# P06_PHY_1.net
KiCad netlist of a schematic drawn in Altium Designer
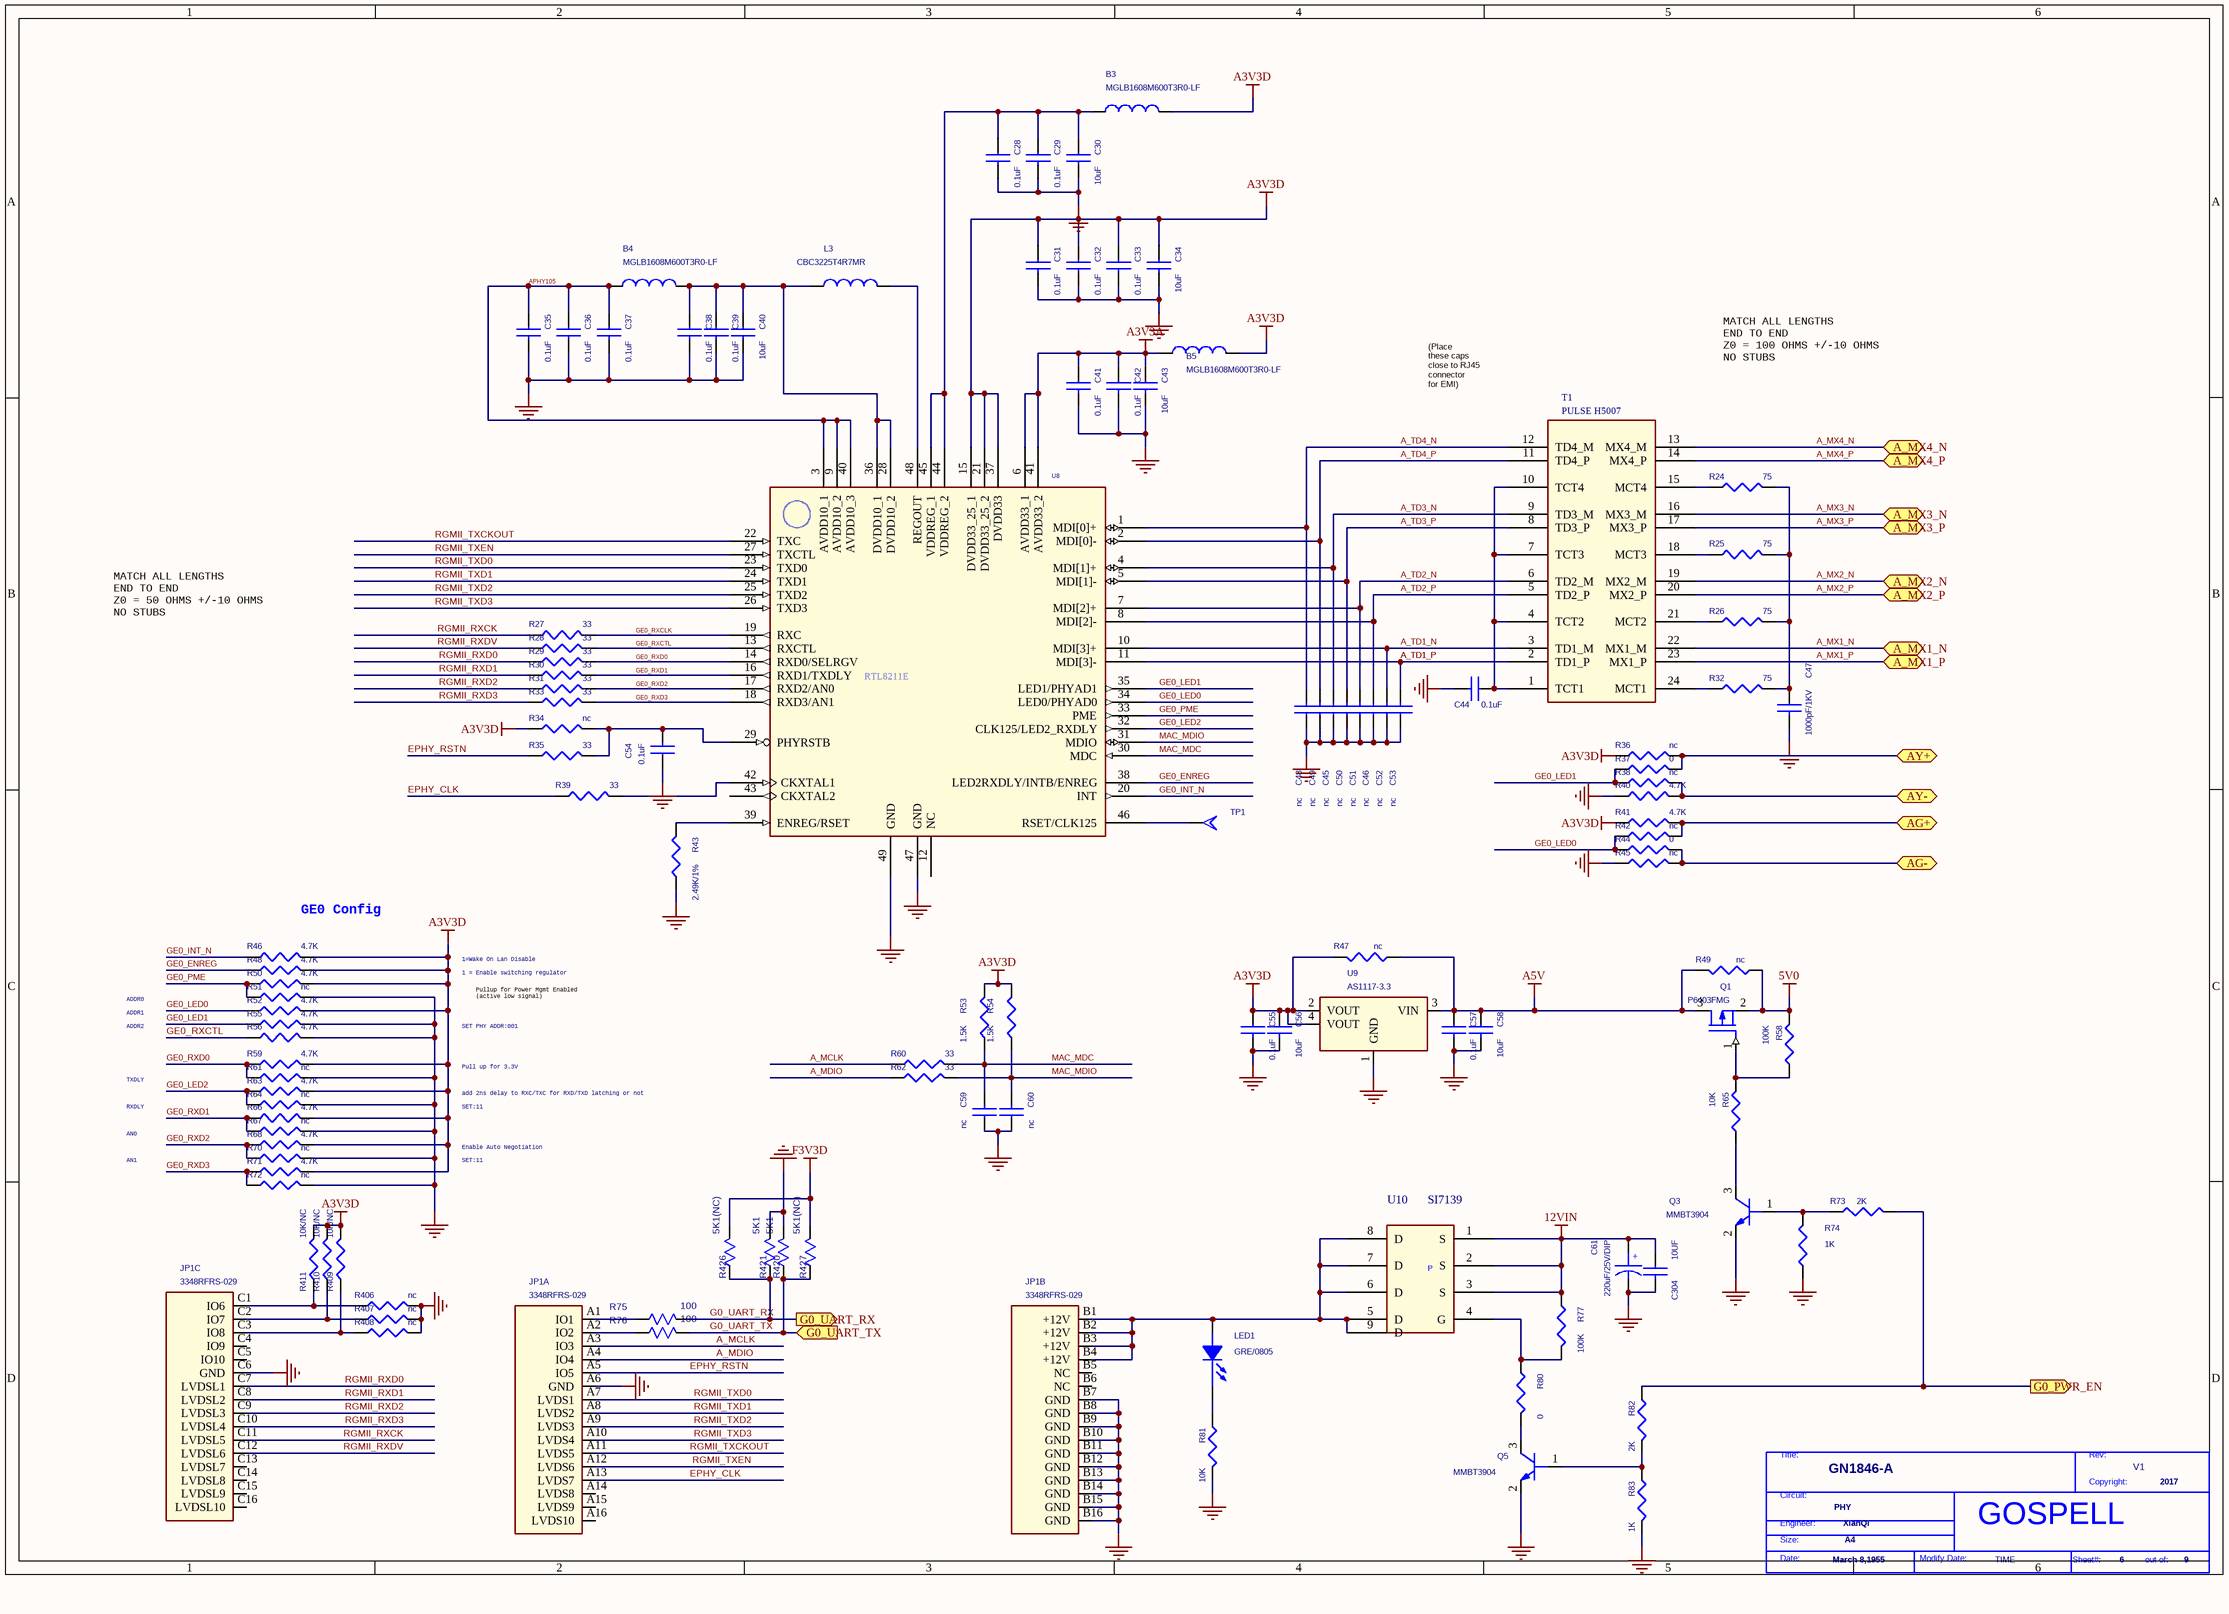
[diagram p0: P06 PHY 1.SchDoc]

(export (version "E")
  (design (tool "Eeschema 10.0.6"))
  (components
    (comp (ref "B3") (value "MGLB1608M600T3R0-LF") (libsource (lib "*") (part "CHOKE TORROID_0")))
    (comp (ref "B4") (value "MGLB1608M600T3R0-LF") (libsource (lib "*") (part "CHOKE TORROID_0")))
    (comp (ref "B5") (value "MGLB1608M600T3R0-LF") (libsource (lib "*") (part "CHOKE TORROID_0")))
    (comp (ref "C28") (value "0.1uF") (libsource (lib "*") (part "CAP NP_Dup1")))
    (comp (ref "C29") (value "0.1uF") (libsource (lib "*") (part "CAP NP_Dup1")))
    (comp (ref "C30") (value "10uF") (libsource (lib "*") (part "CAP NP_Dup1")))
    (comp (ref "C31") (value "0.1uF") (libsource (lib "*") (part "CAP NP_Dup1")))
    (comp (ref "C32") (value "0.1uF") (libsource (lib "*") (part "CAP NP_Dup1")))
    (comp (ref "C33") (value "0.1uF") (libsource (lib "*") (part "CAP NP_Dup1")))
    (comp (ref "C34") (value "10uF") (libsource (lib "*") (part "CAP NP_Dup1")))
    (comp (ref "C35") (value "0.1uF") (libsource (lib "*") (part "CAP NP_Dup1")))
    (comp (ref "C36") (value "0.1uF") (libsource (lib "*") (part "CAP NP_Dup1")))
    (comp (ref "C37") (value "0.1uF") (libsource (lib "*") (part "CAP NP_Dup1")))
    (comp (ref "C38") (value "0.1uF") (libsource (lib "*") (part "CAP NP_Dup1")))
    (comp (ref "C39") (value "0.1uF") (libsource (lib "*") (part "CAP NP_Dup1")))
    (comp (ref "C40") (value "10uF") (libsource (lib "*") (part "CAP NP_Dup1")))
    (comp (ref "C41") (value "0.1uF") (libsource (lib "*") (part "CAP NP_Dup1")))
    (comp (ref "C42") (value "0.1uF") (libsource (lib "*") (part "CAP NP_Dup1")))
    (comp (ref "C43") (value "10uF") (libsource (lib "*") (part "CAP NP_Dup1")))
    (comp (ref "C44") (value "0.1uF") (libsource (lib "*") (part "CAP NP_Dup1")))
    (comp (ref "C45") (value "nc") (libsource (lib "*") (part "CAP NP_Dup1")))
    (comp (ref "C46") (value "nc") (libsource (lib "*") (part "CAP NP_Dup1")))
    (comp (ref "C47") (value "1000pF/1KV") (libsource (lib "*") (part "CAP NP_Dup1")))
    (comp (ref "C48") (value "nc") (libsource (lib "*") (part "CAP NP_Dup1")))
    (comp (ref "C49") (value "nc") (libsource (lib "*") (part "CAP NP_Dup1")))
    (comp (ref "C50") (value "nc") (libsource (lib "*") (part "CAP NP_Dup1")))
    (comp (ref "C51") (value "nc") (libsource (lib "*") (part "CAP NP_Dup1")))
    (comp (ref "C52") (value "nc") (libsource (lib "*") (part "CAP NP_Dup1")))
    (comp (ref "C53") (value "nc") (libsource (lib "*") (part "CAP NP_Dup1")))
    (comp (ref "C54") (value "0.1uF") (libsource (lib "*") (part "CAP NP_Dup1")))
    (comp (ref "C55") (value "0.1uF") (libsource (lib "*") (part "CAP NP_Dup1")))
    (comp (ref "C56") (value "10uF") (libsource (lib "*") (part "CAP NP_Dup1")))
    (comp (ref "C57") (value "0.1uF") (libsource (lib "*") (part "CAP NP_Dup1")))
    (comp (ref "C58") (value "10uF") (libsource (lib "*") (part "CAP NP_Dup1")))
    (comp (ref "C59") (value "nc") (libsource (lib "*") (part "CAP NP_Dup1")))
    (comp (ref "C60") (value "nc") (libsource (lib "*") (part "CAP NP_Dup1")))
    (comp (ref "C61") (value "220uF/25V/DIP") (libsource (lib "*") (part "CAP POL")))
    (comp (ref "C304") (value "10UF") (libsource (lib "*") (part "CAP NP")))
    (comp (ref "JP1")
      (value "3348RFRS-029")
      (footprint "3348RFRS-029")
      (libsource (lib "*") (part "3348RFRS-029"))
    )
    (comp (ref "L3") (value "CBC3225T4R7MR") (libsource (lib "*") (part "CHOKE TORROID_0")))
    (comp (ref "LED1") (value "GRE/0805") (libsource (lib "*") (part "LED_1")))
    (comp (ref "Q1") (value "P6403FMG") (libsource (lib "*") (part "MOSFET P_0")))
    (comp (ref "Q3") (value "MMBT3904") (footprint "SOT23") (libsource (lib "*") (part "2N3904")))
    (comp (ref "Q5") (value "MMBT3904") (footprint "SOT23") (libsource (lib "*") (part "2N3904")))
    (comp (ref "R24") (value "75") (libsource (lib "*") (part "R_Dup1")))
    (comp (ref "R25") (value "75") (libsource (lib "*") (part "R_Dup1")))
    (comp (ref "R26") (value "75") (libsource (lib "*") (part "R_Dup1")))
    (comp (ref "R27") (value "33") (libsource (lib "*") (part "R_Dup1")))
    (comp (ref "R28") (value "33") (libsource (lib "*") (part "R_Dup1")))
    (comp (ref "R29") (value "33") (libsource (lib "*") (part "R_Dup1")))
    (comp (ref "R30") (value "33") (libsource (lib "*") (part "R_Dup1")))
    (comp (ref "R31") (value "33") (libsource (lib "*") (part "R_Dup1")))
    (comp (ref "R32") (value "75") (libsource (lib "*") (part "R_Dup1")))
    (comp (ref "R33") (value "33") (libsource (lib "*") (part "R_Dup1")))
    (comp (ref "R34") (value "nc") (libsource (lib "*") (part "R_Dup1")))
    (comp (ref "R35") (value "33") (libsource (lib "*") (part "R_Dup1")))
    (comp (ref "R36") (value "nc") (libsource (lib "*") (part "R_Dup1")))
    (comp (ref "R37") (value "0") (libsource (lib "*") (part "R_Dup1")))
    (comp (ref "R38") (value "nc") (libsource (lib "*") (part "R_Dup1")))
    (comp (ref "R39") (value "33") (libsource (lib "*") (part "R_Dup1")))
    (comp (ref "R40") (value "4.7K") (libsource (lib "*") (part "R_Dup1")))
    (comp (ref "R41") (value "4.7K") (libsource (lib "*") (part "R_Dup1")))
    (comp (ref "R42") (value "nc") (libsource (lib "*") (part "R_Dup1")))
    (comp (ref "R43") (value "2.49K/1%") (libsource (lib "*") (part "R_Dup1")))
    (comp (ref "R44") (value "0") (libsource (lib "*") (part "R_Dup1")))
    (comp (ref "R45") (value "nc") (libsource (lib "*") (part "R_Dup1")))
    (comp (ref "R46") (value "4.7K") (libsource (lib "*") (part "R_Dup1")))
    (comp (ref "R47") (value "nc") (libsource (lib "*") (part "R")))
    (comp (ref "R48") (value "4.7K") (libsource (lib "*") (part "R_Dup1")))
    (comp (ref "R49") (value "nc") (libsource (lib "*") (part "R")))
    (comp (ref "R50") (value "4.7K") (libsource (lib "*") (part "R_Dup1")))
    (comp (ref "R51") (value "nc") (libsource (lib "*") (part "R_Dup1")))
    (comp (ref "R52") (value "4.7K") (libsource (lib "*") (part "R_Dup1")))
    (comp (ref "R53") (value "1.5K") (libsource (lib "*") (part "R_Dup1")))
    (comp (ref "R54") (value "1.5K") (libsource (lib "*") (part "R_Dup1")))
    (comp (ref "R55") (value "4.7K") (libsource (lib "*") (part "R_Dup1")))
    (comp (ref "R56") (value "4.7K") (libsource (lib "*") (part "R_Dup1")))
    (comp (ref "R58") (value "100K") (libsource (lib "*") (part "R")))
    (comp (ref "R59") (value "4.7K") (libsource (lib "*") (part "R_Dup1")))
    (comp (ref "R60") (value "33") (libsource (lib "*") (part "R_Dup1")))
    (comp (ref "R61") (value "nc") (libsource (lib "*") (part "R_Dup1")))
    (comp (ref "R62") (value "33") (libsource (lib "*") (part "R_Dup1")))
    (comp (ref "R63") (value "4.7K") (libsource (lib "*") (part "R_Dup1")))
    (comp (ref "R64") (value "nc") (libsource (lib "*") (part "R_Dup1")))
    (comp (ref "R65") (value "10K") (libsource (lib "*") (part "R")))
    (comp (ref "R66") (value "4.7K") (libsource (lib "*") (part "R_Dup1")))
    (comp (ref "R67") (value "nc") (libsource (lib "*") (part "R_Dup1")))
    (comp (ref "R68") (value "4.7K") (libsource (lib "*") (part "R_Dup1")))
    (comp (ref "R70") (value "nc") (libsource (lib "*") (part "R_Dup1")))
    (comp (ref "R71") (value "4.7K") (libsource (lib "*") (part "R_Dup1")))
    (comp (ref "R72") (value "nc") (libsource (lib "*") (part "R_Dup1")))
    (comp (ref "R73") (value "2K") (libsource (lib "*") (part "R")))
    (comp (ref "R74") (value "1K") (libsource (lib "*") (part "R")))
    (comp (ref "R75") (value "100") (libsource (lib "*") (part "R_1")))
    (comp (ref "R76") (value "100") (libsource (lib "*") (part "R_1")))
    (comp (ref "R77") (value "100K") (libsource (lib "*") (part "R_Dup1")))
    (comp (ref "R80") (value "0") (libsource (lib "*") (part "R_Dup1")))
    (comp (ref "R81") (value "10K") (libsource (lib "*") (part "R_Dup1")))
    (comp (ref "R82") (value "2K") (libsource (lib "*") (part "R_Dup1")))
    (comp (ref "R83") (value "1K") (libsource (lib "*") (part "R_Dup1")))
    (comp (ref "R406") (value "nc") (libsource (lib "*") (part "R_Dup1")))
    (comp (ref "R407") (value "nc") (libsource (lib "*") (part "R_Dup1")))
    (comp (ref "R408") (value "nc") (libsource (lib "*") (part "R_Dup1")))
    (comp (ref "R409") (value "10K/NC") (libsource (lib "*") (part "R_Dup1")))
    (comp (ref "R410") (value "10K/NC") (libsource (lib "*") (part "R_Dup1")))
    (comp (ref "R411") (value "10K/NC") (libsource (lib "*") (part "R_Dup1")))
    (comp (ref "R420") (value "5K1") (libsource (lib "*") (part "R_1")))
    (comp (ref "R421") (value "5K1") (libsource (lib "*") (part "R_1")))
    (comp (ref "R426") (value "5K1(NC)") (libsource (lib "*") (part "R_1")))
    (comp (ref "R427") (value "5K1(NC)") (libsource (lib "*") (part "R_1")))
    (comp (ref "T1") (value "PULSE H5007") (footprint "H5007-H") (libsource (lib "*") (part "PULSE H5007_0")))
    (comp (ref "TP1") (value "T POINT A") (libsource (lib "*") (part "T POINT A")))
    (comp (ref "U8")
      (value "RTL8211D")
      (footprint "QFN-48P-RTL8211")
      (libsource (lib "*") (part "RTL8211D_2"))
    )
    (comp (ref "U9") (value "AS1117-3.3") (footprint "SOT223") (libsource (lib "*") (part "AS1117-X_3")))
    (comp (ref "U10")
      (value "SI7139")
      (footprint "PowerPAKSO8")
      (libsource (lib "GN-1846-A-V1_Library") (part "SI7139"))
    )
  )
  (nets
    (net (code "1") (name "/AG+") (class "Default")
      (node (ref "R41") (pin "2") (pinfunction "2_2") (pintype "passive"))
      (node (ref "R42") (pin "2") (pinfunction "2_2") (pintype "passive"))
    )
    (net (code "2") (name "/AG-") (class "Default")
      (node (ref "R44") (pin "2") (pinfunction "2_2") (pintype "passive"))
      (node (ref "R45") (pin "2") (pinfunction "2_2") (pintype "passive"))
    )
    (net (code "3") (name "/APHY105") (class "Default")
      (node (ref "B4") (pin "1") (pinfunction "1_1") (pintype "passive"))
      (node (ref "C35") (pin "1") (pinfunction "1_1") (pintype "passive"))
      (node (ref "C36") (pin "1") (pinfunction "1_1") (pintype "passive"))
      (node (ref "C37") (pin "1") (pinfunction "1_1") (pintype "passive"))
      (node (ref "U8") (pin "3") (pinfunction "AVDD10_1_3") (pintype "power_in"))
      (node (ref "U8") (pin "40") (pinfunction "AVDD10_3_40") (pintype "power_in"))
      (node (ref "U8") (pin "9") (pinfunction "AVDD10_2_9") (pintype "power_in"))
    )
    (net (code "4") (name "/AY+") (class "Default")
      (node (ref "R36") (pin "2") (pinfunction "2_2") (pintype "passive"))
      (node (ref "R37") (pin "2") (pinfunction "2_2") (pintype "passive"))
    )
    (net (code "5") (name "/AY-") (class "Default")
      (node (ref "R38") (pin "2") (pinfunction "2_2") (pintype "passive"))
      (node (ref "R40") (pin "2") (pinfunction "2_2") (pintype "passive"))
    )
    (net (code "6") (name "/A_MCLK") (class "Default")
      (node (ref "JP1") (pin "A3") (pinfunction "IO3_A3") (pintype "passive"))
      (node (ref "R60") (pin "1") (pinfunction "1_1") (pintype "passive"))
    )
    (net (code "7") (name "/A_MDIO") (class "Default")
      (node (ref "JP1") (pin "A4") (pinfunction "IO4_A4") (pintype "passive"))
      (node (ref "R62") (pin "1") (pinfunction "1_1") (pintype "passive"))
    )
    (net (code "8") (name "/A_MX1_N") (class "Default")
      (node (ref "T1") (pin "22") (pinfunction "MX1_M_22") (pintype "passive"))
    )
    (net (code "9") (name "/A_MX1_P") (class "Default")
      (node (ref "T1") (pin "23") (pinfunction "MX1_P_23") (pintype "passive"))
    )
    (net (code "10") (name "/A_MX2_N") (class "Default")
      (node (ref "T1") (pin "19") (pinfunction "MX2_M_19") (pintype "passive"))
    )
    (net (code "11") (name "/A_MX2_P") (class "Default")
      (node (ref "T1") (pin "20") (pinfunction "MX2_P_20") (pintype "passive"))
    )
    (net (code "12") (name "/A_MX3_N") (class "Default")
      (node (ref "T1") (pin "16") (pinfunction "MX3_M_16") (pintype "passive"))
    )
    (net (code "13") (name "/A_MX3_P") (class "Default")
      (node (ref "T1") (pin "17") (pinfunction "MX3_P_17") (pintype "passive"))
    )
    (net (code "14") (name "/A_MX4_N") (class "Default")
      (node (ref "T1") (pin "13") (pinfunction "MX4_M_13") (pintype "passive"))
    )
    (net (code "15") (name "/A_MX4_P") (class "Default")
      (node (ref "T1") (pin "14") (pinfunction "MX4_P_14") (pintype "passive"))
    )
    (net (code "16") (name "/A_TD1_N") (class "Default")
      (node (ref "C52") (pin "2") (pinfunction "2_2") (pintype "passive"))
      (node (ref "T1") (pin "3") (pinfunction "TD1_M_3") (pintype "passive"))
      (node (ref "U8") (pin "10") (pinfunction "MDI[3]+_10") (pintype "passive"))
    )
    (net (code "17") (name "/A_TD1_P") (class "Default")
      (node (ref "C53") (pin "2") (pinfunction "2_2") (pintype "passive"))
      (node (ref "T1") (pin "2") (pinfunction "TD1_P_2") (pintype "passive"))
      (node (ref "U8") (pin "11") (pinfunction "MDI[3]-_11") (pintype "passive"))
    )
    (net (code "18") (name "/A_TD2_N") (class "Default")
      (node (ref "C51") (pin "2") (pinfunction "2_2") (pintype "passive"))
      (node (ref "T1") (pin "6") (pinfunction "TD2_M_6") (pintype "passive"))
      (node (ref "U8") (pin "7") (pinfunction "MDI[2]+_7") (pintype "passive"))
    )
    (net (code "19") (name "/A_TD2_P") (class "Default")
      (node (ref "C46") (pin "2") (pinfunction "2_2") (pintype "passive"))
      (node (ref "T1") (pin "5") (pinfunction "TD2_P_5") (pintype "passive"))
      (node (ref "U8") (pin "8") (pinfunction "MDI[2]-_8") (pintype "passive"))
    )
    (net (code "20") (name "/A_TD3_N") (class "Default")
      (node (ref "C45") (pin "2") (pinfunction "2_2") (pintype "passive"))
      (node (ref "T1") (pin "9") (pinfunction "TD3_M_9") (pintype "passive"))
      (node (ref "U8") (pin "4") (pinfunction "MDI[1]+_4") (pintype "bidirectional"))
    )
    (net (code "21") (name "/A_TD3_P") (class "Default")
      (node (ref "C50") (pin "2") (pinfunction "2_2") (pintype "passive"))
      (node (ref "T1") (pin "8") (pinfunction "TD3_P_8") (pintype "passive"))
      (node (ref "U8") (pin "5") (pinfunction "MDI[1]-_5") (pintype "bidirectional"))
    )
    (net (code "22") (name "/A_TD4_N") (class "Default")
      (node (ref "C48") (pin "2") (pinfunction "2_2") (pintype "passive"))
      (node (ref "T1") (pin "12") (pinfunction "TD4_M_12") (pintype "passive"))
      (node (ref "U8") (pin "1") (pinfunction "MDI[0]+_1") (pintype "bidirectional"))
    )
    (net (code "23") (name "/A_TD4_P") (class "Default")
      (node (ref "C49") (pin "2") (pinfunction "2_2") (pintype "passive"))
      (node (ref "T1") (pin "11") (pinfunction "TD4_P_11") (pintype "passive"))
      (node (ref "U8") (pin "2") (pinfunction "MDI[0]-_2") (pintype "bidirectional"))
    )
    (net (code "24") (name "/EPHY_CLK") (class "Default")
      (node (ref "JP1") (pin "A13") (pinfunction "LVDS7_A13") (pintype "passive"))
      (node (ref "R39") (pin "1") (pinfunction "1_1") (pintype "passive"))
    )
    (net (code "25") (name "/EPHY_RSTN") (class "Default")
      (node (ref "JP1") (pin "A5") (pinfunction "IO5_A5") (pintype "passive"))
      (node (ref "R35") (pin "1") (pinfunction "1_1") (pintype "passive"))
    )
    (net (code "26") (name "/G0_PWR_EN") (class "Default")
      (node (ref "R73") (pin "2") (pinfunction "2_2") (pintype "passive"))
      (node (ref "R82") (pin "2") (pinfunction "2_2") (pintype "passive"))
    )
    (net (code "27") (name "/G0_UART_RX") (class "Default")
      (node (ref "R421") (pin "1") (pinfunction "A_1") (pintype "passive"))
      (node (ref "R426") (pin "1") (pinfunction "A_1") (pintype "passive"))
      (node (ref "R75") (pin "2") (pinfunction "B_2") (pintype "passive"))
    )
    (net (code "28") (name "/G0_UART_TX") (class "Default")
      (node (ref "R420") (pin "1") (pinfunction "A_1") (pintype "passive"))
      (node (ref "R427") (pin "1") (pinfunction "A_1") (pintype "passive"))
      (node (ref "R76") (pin "2") (pinfunction "B_2") (pintype "passive"))
    )
    (net (code "29") (name "/GE0_ENREG") (class "Default")
      (node (ref "R48") (pin "1") (pinfunction "1_1") (pintype "passive"))
      (node (ref "U8") (pin "38") (pinfunction "LED2RXDLY/INTB/ENREG_38") (pintype "passive"))
    )
    (net (code "30") (name "/GE0_INT_N") (class "Default")
      (node (ref "R46") (pin "1") (pinfunction "1_1") (pintype "passive"))
      (node (ref "U8") (pin "20") (pinfunction "INT_20") (pintype "output"))
    )
    (net (code "31") (name "/GE0_LED0") (class "Default")
      (node (ref "R42") (pin "1") (pinfunction "1_1") (pintype "passive"))
      (node (ref "R44") (pin "1") (pinfunction "1_1") (pintype "passive"))
      (node (ref "R52") (pin "1") (pinfunction "1_1") (pintype "passive"))
      (node (ref "U8") (pin "34") (pinfunction "LED0/PHYAD0_34") (pintype "output"))
    )
    (net (code "32") (name "/GE0_LED1") (class "Default")
      (node (ref "R37") (pin "1") (pinfunction "1_1") (pintype "passive"))
      (node (ref "R38") (pin "1") (pinfunction "1_1") (pintype "passive"))
      (node (ref "R55") (pin "1") (pinfunction "1_1") (pintype "passive"))
      (node (ref "U8") (pin "35") (pinfunction "LED1/PHYAD1_35") (pintype "output"))
    )
    (net (code "33") (name "/GE0_LED2") (class "Default")
      (node (ref "R63") (pin "1") (pinfunction "1_1") (pintype "passive"))
      (node (ref "R64") (pin "1") (pinfunction "1_1") (pintype "passive"))
      (node (ref "U8") (pin "32") (pinfunction "CLK125/LED2_RXDLY_32") (pintype "output"))
    )
    (net (code "34") (name "/GE0_PME") (class "Default")
      (node (ref "R50") (pin "1") (pinfunction "1_1") (pintype "passive"))
      (node (ref "R51") (pin "1") (pinfunction "1_1") (pintype "passive"))
      (node (ref "U8") (pin "33") (pinfunction "PME_33") (pintype "output"))
    )
    (net (code "35") (name "/GE0_RXCLK") (class "Default")
      (node (ref "R27") (pin "2") (pinfunction "2_2") (pintype "passive"))
      (node (ref "U8") (pin "19") (pinfunction "RXC_19") (pintype "output"))
    )
    (net (code "36") (name "/GE0_RXCTL") (class "Default")
      (node (ref "R28") (pin "2") (pinfunction "2_2") (pintype "passive"))
      (node (ref "R56") (pin "1") (pinfunction "1_1") (pintype "passive"))
      (node (ref "U8") (pin "13") (pinfunction "RXCTL_13") (pintype "output"))
    )
    (net (code "37") (name "/GE0_RXD0") (class "Default")
      (node (ref "R29") (pin "2") (pinfunction "2_2") (pintype "passive"))
      (node (ref "R59") (pin "1") (pinfunction "1_1") (pintype "passive"))
      (node (ref "R61") (pin "1") (pinfunction "1_1") (pintype "passive"))
      (node (ref "U8") (pin "14") (pinfunction "RXD0/SELRGV_14") (pintype "output"))
    )
    (net (code "38") (name "/GE0_RXD1") (class "Default")
      (node (ref "R30") (pin "2") (pinfunction "2_2") (pintype "passive"))
      (node (ref "R66") (pin "1") (pinfunction "1_1") (pintype "passive"))
      (node (ref "R67") (pin "1") (pinfunction "1_1") (pintype "passive"))
      (node (ref "U8") (pin "16") (pinfunction "RXD1/TXDLY_16") (pintype "output"))
    )
    (net (code "39") (name "/GE0_RXD2") (class "Default")
      (node (ref "R31") (pin "2") (pinfunction "2_2") (pintype "passive"))
      (node (ref "R68") (pin "1") (pinfunction "1_1") (pintype "passive"))
      (node (ref "R70") (pin "1") (pinfunction "1_1") (pintype "passive"))
      (node (ref "U8") (pin "17") (pinfunction "RXD2/AN0_17") (pintype "output"))
    )
    (net (code "40") (name "/GE0_RXD3") (class "Default")
      (node (ref "R33") (pin "2") (pinfunction "2_2") (pintype "passive"))
      (node (ref "R71") (pin "1") (pinfunction "1_1") (pintype "passive"))
      (node (ref "R72") (pin "1") (pinfunction "1_1") (pintype "passive"))
      (node (ref "U8") (pin "18") (pinfunction "RXD3/AN1_18") (pintype "output"))
    )
    (net (code "41") (name "/MAC_MDC") (class "Default")
      (node (ref "C59") (pin "2") (pinfunction "2_2") (pintype "passive"))
      (node (ref "R53") (pin "1") (pinfunction "1_1") (pintype "passive"))
      (node (ref "R60") (pin "2") (pinfunction "2_2") (pintype "passive"))
      (node (ref "U8") (pin "30") (pinfunction "MDC_30") (pintype "input"))
    )
    (net (code "42") (name "/MAC_MDIO") (class "Default")
      (node (ref "C60") (pin "2") (pinfunction "2_2") (pintype "passive"))
      (node (ref "R54") (pin "1") (pinfunction "1_1") (pintype "passive"))
      (node (ref "R62") (pin "2") (pinfunction "2_2") (pintype "passive"))
      (node (ref "U8") (pin "31") (pinfunction "MDIO_31") (pintype "bidirectional"))
    )
    (net (code "43") (name "/RGMII_RXCK") (class "Default")
      (node (ref "JP1") (pin "C11") (pinfunction "LVDSL5_C11") (pintype "passive"))
      (node (ref "R27") (pin "1") (pinfunction "1_1") (pintype "passive"))
    )
    (net (code "44") (name "/RGMII_RXD0") (class "Default")
      (node (ref "JP1") (pin "C7") (pinfunction "LVDSL1_C7") (pintype "passive"))
      (node (ref "R29") (pin "1") (pinfunction "1_1") (pintype "passive"))
    )
    (net (code "45") (name "/RGMII_RXD1") (class "Default")
      (node (ref "JP1") (pin "C8") (pinfunction "LVDSL2_C8") (pintype "passive"))
      (node (ref "R30") (pin "1") (pinfunction "1_1") (pintype "passive"))
    )
    (net (code "46") (name "/RGMII_RXD2") (class "Default")
      (node (ref "JP1") (pin "C9") (pinfunction "LVDSL3_C9") (pintype "passive"))
      (node (ref "R31") (pin "1") (pinfunction "1_1") (pintype "passive"))
    )
    (net (code "47") (name "/RGMII_RXD3") (class "Default")
      (node (ref "JP1") (pin "C10") (pinfunction "LVDSL4_C10") (pintype "passive"))
      (node (ref "R33") (pin "1") (pinfunction "1_1") (pintype "passive"))
    )
    (net (code "48") (name "/RGMII_RXDV") (class "Default")
      (node (ref "JP1") (pin "C12") (pinfunction "LVDSL6_C12") (pintype "passive"))
      (node (ref "R28") (pin "1") (pinfunction "1_1") (pintype "passive"))
    )
    (net (code "49") (name "/RGMII_TXCKOUT") (class "Default")
      (node (ref "JP1") (pin "A11") (pinfunction "LVDS5_A11") (pintype "passive"))
      (node (ref "U8") (pin "22") (pinfunction "TXC_22") (pintype "input"))
    )
    (net (code "50") (name "/RGMII_TXD0") (class "Default")
      (node (ref "JP1") (pin "A7") (pinfunction "LVDS1_A7") (pintype "passive"))
      (node (ref "U8") (pin "23") (pinfunction "TXD0_23") (pintype "input"))
    )
    (net (code "51") (name "/RGMII_TXD1") (class "Default")
      (node (ref "JP1") (pin "A8") (pinfunction "LVDS2_A8") (pintype "passive"))
      (node (ref "U8") (pin "24") (pinfunction "TXD1_24") (pintype "input"))
    )
    (net (code "52") (name "/RGMII_TXD2") (class "Default")
      (node (ref "JP1") (pin "A9") (pinfunction "LVDS3_A9") (pintype "passive"))
      (node (ref "U8") (pin "25") (pinfunction "TXD2_25") (pintype "input"))
    )
    (net (code "53") (name "/RGMII_TXD3") (class "Default")
      (node (ref "JP1") (pin "A10") (pinfunction "LVDS4_A10") (pintype "passive"))
      (node (ref "U8") (pin "26") (pinfunction "TXD3_26") (pintype "input"))
    )
    (net (code "54") (name "/RGMII_TXEN") (class "Default")
      (node (ref "JP1") (pin "A12") (pinfunction "LVDS6_A12") (pintype "passive"))
      (node (ref "U8") (pin "27") (pinfunction "TXCTL_27") (pintype "input"))
    )
    (net (code "55") (name "5V0") (class "Default")
      (node (ref "Q1") (pin "2") (pinfunction "SOURCE_2") (pintype "passive"))
      (node (ref "R49") (pin "2") (pinfunction "2_2") (pintype "passive"))
      (node (ref "R58") (pin "1") (pinfunction "1_1") (pintype "passive"))
    )
    (net (code "56") (name "12VIN") (class "Default")
      (node (ref "C304") (pin "1") (pinfunction "1_1") (pintype "passive"))
      (node (ref "C61") (pin "1") (pinfunction "1_1") (pintype "passive"))
      (node (ref "R77") (pin "2") (pinfunction "2_2") (pintype "passive"))
      (node (ref "U10") (pin "1") (pinfunction "S_1") (pintype "passive"))
      (node (ref "U10") (pin "2") (pinfunction "S_2") (pintype "passive"))
      (node (ref "U10") (pin "3") (pinfunction "S_3") (pintype "passive"))
    )
    (net (code "57") (name "A3V3A") (class "Default")
      (node (ref "B5") (pin "1") (pinfunction "1_1") (pintype "passive"))
      (node (ref "C41") (pin "1") (pinfunction "1_1") (pintype "passive"))
      (node (ref "C42") (pin "1") (pinfunction "1_1") (pintype "passive"))
      (node (ref "C43") (pin "1") (pinfunction "1_1") (pintype "passive"))
      (node (ref "U8") (pin "41") (pinfunction "AVDD33_2_41") (pintype "power_in"))
      (node (ref "U8") (pin "6") (pinfunction "AVDD33_1_6") (pintype "power_in"))
    )
    (net (code "58") (name "A3V3D") (class "Default")
      (node (ref "B3") (pin "2") (pinfunction "2_2") (pintype "passive"))
      (node (ref "B5") (pin "2") (pinfunction "2_2") (pintype "passive"))
      (node (ref "C31") (pin "1") (pinfunction "1_1") (pintype "passive"))
      (node (ref "C32") (pin "1") (pinfunction "1_1") (pintype "passive"))
      (node (ref "C33") (pin "1") (pinfunction "1_1") (pintype "passive"))
      (node (ref "C34") (pin "1") (pinfunction "1_1") (pintype "passive"))
      (node (ref "C55") (pin "1") (pinfunction "1_1") (pintype "passive"))
      (node (ref "C56") (pin "1") (pinfunction "1_1") (pintype "passive"))
      (node (ref "R34") (pin "1") (pinfunction "1_1") (pintype "passive"))
      (node (ref "R36") (pin "1") (pinfunction "1_1") (pintype "passive"))
      (node (ref "R409") (pin "2") (pinfunction "2_2") (pintype "passive"))
      (node (ref "R41") (pin "1") (pinfunction "1_1") (pintype "passive"))
      (node (ref "R410") (pin "2") (pinfunction "2_2") (pintype "passive"))
      (node (ref "R411") (pin "2") (pinfunction "2_2") (pintype "passive"))
      (node (ref "R46") (pin "2") (pinfunction "2_2") (pintype "passive"))
      (node (ref "R47") (pin "1") (pinfunction "1_1") (pintype "passive"))
      (node (ref "R48") (pin "2") (pinfunction "2_2") (pintype "passive"))
      (node (ref "R50") (pin "2") (pinfunction "2_2") (pintype "passive"))
      (node (ref "R52") (pin "2") (pinfunction "2_2") (pintype "passive"))
      (node (ref "R53") (pin "2") (pinfunction "2_2") (pintype "passive"))
      (node (ref "R54") (pin "2") (pinfunction "2_2") (pintype "passive"))
      (node (ref "R59") (pin "2") (pinfunction "2_2") (pintype "passive"))
      (node (ref "R63") (pin "2") (pinfunction "2_2") (pintype "passive"))
      (node (ref "R66") (pin "2") (pinfunction "2_2") (pintype "passive"))
      (node (ref "R68") (pin "2") (pinfunction "2_2") (pintype "passive"))
      (node (ref "R71") (pin "2") (pinfunction "2_2") (pintype "passive"))
      (node (ref "U8") (pin "15") (pinfunction "DVDD33_25_1_15") (pintype "power_in"))
      (node (ref "U8") (pin "21") (pinfunction "DVDD33_25_2_21") (pintype "power_in"))
      (node (ref "U8") (pin "37") (pinfunction "DVDD33_37") (pintype "power_in"))
      (node (ref "U9") (pin "2") (pinfunction "VOUT_2") (pintype "passive"))
      (node (ref "U9") (pin "4") (pinfunction "VOUT_4") (pintype "passive"))
    )
    (net (code "59") (name "A5V") (class "Default")
      (node (ref "C57") (pin "1") (pinfunction "1_1") (pintype "passive"))
      (node (ref "C58") (pin "1") (pinfunction "1_1") (pintype "passive"))
      (node (ref "Q1") (pin "3") (pinfunction "DRAIN_3") (pintype "passive"))
      (node (ref "R47") (pin "2") (pinfunction "2_2") (pintype "passive"))
      (node (ref "R49") (pin "1") (pinfunction "1_1") (pintype "passive"))
      (node (ref "U9") (pin "3") (pinfunction "VIN_3") (pintype "passive"))
    )
    (net (code "60") (name "F3V3D") (class "Default")
      (node (ref "R426") (pin "2") (pinfunction "B_2") (pintype "passive"))
      (node (ref "R427") (pin "2") (pinfunction "B_2") (pintype "passive"))
    )
    (net (code "61") (name "GND") (class "Default")
      (node (ref "C28") (pin "2") (pinfunction "2_2") (pintype "passive"))
      (node (ref "C29") (pin "2") (pinfunction "2_2") (pintype "passive"))
      (node (ref "C30") (pin "2") (pinfunction "2_2") (pintype "passive"))
      (node (ref "C304") (pin "2") (pinfunction "2_2") (pintype "passive"))
      (node (ref "C31") (pin "2") (pinfunction "2_2") (pintype "passive"))
      (node (ref "C32") (pin "2") (pinfunction "2_2") (pintype "passive"))
      (node (ref "C33") (pin "2") (pinfunction "2_2") (pintype "passive"))
      (node (ref "C34") (pin "2") (pinfunction "2_2") (pintype "passive"))
      (node (ref "C35") (pin "2") (pinfunction "2_2") (pintype "passive"))
      (node (ref "C36") (pin "2") (pinfunction "2_2") (pintype "passive"))
      (node (ref "C37") (pin "2") (pinfunction "2_2") (pintype "passive"))
      (node (ref "C38") (pin "2") (pinfunction "2_2") (pintype "passive"))
      (node (ref "C39") (pin "2") (pinfunction "2_2") (pintype "passive"))
      (node (ref "C40") (pin "2") (pinfunction "2_2") (pintype "passive"))
      (node (ref "C41") (pin "2") (pinfunction "2_2") (pintype "passive"))
      (node (ref "C42") (pin "2") (pinfunction "2_2") (pintype "passive"))
      (node (ref "C43") (pin "2") (pinfunction "2_2") (pintype "passive"))
      (node (ref "C44") (pin "2") (pinfunction "2_2") (pintype "passive"))
      (node (ref "C45") (pin "1") (pinfunction "1_1") (pintype "passive"))
      (node (ref "C46") (pin "1") (pinfunction "1_1") (pintype "passive"))
      (node (ref "C47") (pin "2") (pinfunction "2_2") (pintype "passive"))
      (node (ref "C48") (pin "1") (pinfunction "1_1") (pintype "passive"))
      (node (ref "C49") (pin "1") (pinfunction "1_1") (pintype "passive"))
      (node (ref "C50") (pin "1") (pinfunction "1_1") (pintype "passive"))
      (node (ref "C51") (pin "1") (pinfunction "1_1") (pintype "passive"))
      (node (ref "C52") (pin "1") (pinfunction "1_1") (pintype "passive"))
      (node (ref "C53") (pin "1") (pinfunction "1_1") (pintype "passive"))
      (node (ref "C54") (pin "1") (pinfunction "1_1") (pintype "passive"))
      (node (ref "C55") (pin "2") (pinfunction "2_2") (pintype "passive"))
      (node (ref "C56") (pin "2") (pinfunction "2_2") (pintype "passive"))
      (node (ref "C57") (pin "2") (pinfunction "2_2") (pintype "passive"))
      (node (ref "C58") (pin "2") (pinfunction "2_2") (pintype "passive"))
      (node (ref "C59") (pin "1") (pinfunction "1_1") (pintype "passive"))
      (node (ref "C60") (pin "1") (pinfunction "1_1") (pintype "passive"))
      (node (ref "C61") (pin "2") (pinfunction "2_2") (pintype "passive"))
      (node (ref "JP1") (pin "A6") (pinfunction "GND_A6") (pintype "passive"))
      (node (ref "JP1") (pin "B10") (pinfunction "GND_B10") (pintype "passive"))
      (node (ref "JP1") (pin "B11") (pinfunction "GND_B11") (pintype "passive"))
      (node (ref "JP1") (pin "B12") (pinfunction "GND_B12") (pintype "passive"))
      (node (ref "JP1") (pin "B13") (pinfunction "GND_B13") (pintype "passive"))
      (node (ref "JP1") (pin "B14") (pinfunction "GND_B14") (pintype "passive"))
      (node (ref "JP1") (pin "B15") (pinfunction "GND_B15") (pintype "passive"))
      (node (ref "JP1") (pin "B16") (pinfunction "GND_B16") (pintype "passive"))
      (node (ref "JP1") (pin "B7") (pinfunction "GND_B7") (pintype "passive"))
      (node (ref "JP1") (pin "B8") (pinfunction "GND_B8") (pintype "passive"))
      (node (ref "JP1") (pin "B9") (pinfunction "GND_B9") (pintype "passive"))
      (node (ref "JP1") (pin "C6") (pinfunction "GND_C6") (pintype "passive"))
      (node (ref "Q3") (pin "2") (pinfunction "EMITTER_2") (pintype "passive"))
      (node (ref "Q5") (pin "2") (pinfunction "EMITTER_2") (pintype "passive"))
      (node (ref "R40") (pin "1") (pinfunction "1_1") (pintype "passive"))
      (node (ref "R406") (pin "2") (pinfunction "2_2") (pintype "passive"))
      (node (ref "R407") (pin "2") (pinfunction "2_2") (pintype "passive"))
      (node (ref "R408") (pin "2") (pinfunction "2_2") (pintype "passive"))
      (node (ref "R420") (pin "2") (pinfunction "B_2") (pintype "passive"))
      (node (ref "R421") (pin "2") (pinfunction "B_2") (pintype "passive"))
      (node (ref "R43") (pin "1") (pinfunction "1_1") (pintype "passive"))
      (node (ref "R45") (pin "1") (pinfunction "1_1") (pintype "passive"))
      (node (ref "R51") (pin "2") (pinfunction "2_2") (pintype "passive"))
      (node (ref "R55") (pin "2") (pinfunction "2_2") (pintype "passive"))
      (node (ref "R56") (pin "2") (pinfunction "2_2") (pintype "passive"))
      (node (ref "R61") (pin "2") (pinfunction "2_2") (pintype "passive"))
      (node (ref "R64") (pin "2") (pinfunction "2_2") (pintype "passive"))
      (node (ref "R67") (pin "2") (pinfunction "2_2") (pintype "passive"))
      (node (ref "R70") (pin "2") (pinfunction "2_2") (pintype "passive"))
      (node (ref "R72") (pin "2") (pinfunction "2_2") (pintype "passive"))
      (node (ref "R74") (pin "1") (pinfunction "1_1") (pintype "passive"))
      (node (ref "R81") (pin "1") (pinfunction "1_1") (pintype "passive"))
      (node (ref "R83") (pin "1") (pinfunction "1_1") (pintype "passive"))
      (node (ref "U8") (pin "47") (pinfunction "GND_47") (pintype "power_in"))
      (node (ref "U8") (pin "49") (pinfunction "GND_49") (pintype "power_in"))
      (node (ref "U9") (pin "1") (pinfunction "GND_1") (pintype "passive"))
    )
    (net (code "62") (name "Net-(C47-Pad1)") (class "Default")
      (node (ref "C47") (pin "1") (pinfunction "1_1") (pintype "passive"))
      (node (ref "R24") (pin "2") (pinfunction "2_2") (pintype "passive"))
      (node (ref "R25") (pin "2") (pinfunction "2_2") (pintype "passive"))
      (node (ref "R26") (pin "2") (pinfunction "2_2") (pintype "passive"))
      (node (ref "R32") (pin "2") (pinfunction "2_2") (pintype "passive"))
    )
    (net (code "63") (name "Net-(JP1A-IO1)") (class "Default")
      (node (ref "JP1") (pin "A1") (pinfunction "IO1_A1") (pintype "passive"))
      (node (ref "R75") (pin "1") (pinfunction "A_1") (pintype "passive"))
    )
    (net (code "64") (name "Net-(JP1A-IO2)") (class "Default")
      (node (ref "JP1") (pin "A2") (pinfunction "IO2_A2") (pintype "passive"))
      (node (ref "R76") (pin "1") (pinfunction "A_1") (pintype "passive"))
    )
    (net (code "65") (name "Net-(JP1C-IO6)") (class "Default")
      (node (ref "JP1") (pin "C1") (pinfunction "IO6_C1") (pintype "passive"))
      (node (ref "R406") (pin "1") (pinfunction "1_1") (pintype "passive"))
      (node (ref "R411") (pin "1") (pinfunction "1_1") (pintype "passive"))
    )
    (net (code "66") (name "Net-(JP1C-IO7)") (class "Default")
      (node (ref "JP1") (pin "C2") (pinfunction "IO7_C2") (pintype "passive"))
      (node (ref "R407") (pin "1") (pinfunction "1_1") (pintype "passive"))
      (node (ref "R410") (pin "1") (pinfunction "1_1") (pintype "passive"))
    )
    (net (code "67") (name "Net-(JP1C-IO8)") (class "Default")
      (node (ref "JP1") (pin "C3") (pinfunction "IO8_C3") (pintype "passive"))
      (node (ref "R408") (pin "1") (pinfunction "1_1") (pintype "passive"))
      (node (ref "R409") (pin "1") (pinfunction "1_1") (pintype "passive"))
    )
    (net (code "68") (name "Net-(LED1-ANODE)") (class "Default")
      (node (ref "JP1") (pin "B1") (pinfunction "+12V_B1") (pintype "passive"))
      (node (ref "JP1") (pin "B2") (pinfunction "+12V_B2") (pintype "passive"))
      (node (ref "JP1") (pin "B3") (pinfunction "+12V_B3") (pintype "passive"))
      (node (ref "JP1") (pin "B4") (pinfunction "+12V_B4") (pintype "passive"))
      (node (ref "LED1") (pin "A") (pinfunction "ANODE_A") (pintype "passive"))
      (node (ref "U10") (pin "5") (pinfunction "D_5") (pintype "passive"))
      (node (ref "U10") (pin "6") (pinfunction "D_6") (pintype "passive"))
      (node (ref "U10") (pin "7") (pinfunction "D_7") (pintype "passive"))
      (node (ref "U10") (pin "8") (pinfunction "D_8") (pintype "passive"))
      (node (ref "U10") (pin "9") (pinfunction "D_9") (pintype "passive"))
    )
    (net (code "69") (name "Net-(LED1-CATHODE)") (class "Default")
      (node (ref "LED1") (pin "K") (pinfunction "CATHODE_K") (pintype "passive"))
      (node (ref "R81") (pin "2") (pinfunction "2_2") (pintype "passive"))
    )
    (net (code "70") (name "Net-(Q1-GATE)") (class "Default")
      (node (ref "Q1") (pin "1") (pinfunction "GATE_1") (pintype "input"))
      (node (ref "R58") (pin "2") (pinfunction "2_2") (pintype "passive"))
      (node (ref "R65") (pin "1") (pinfunction "1_1") (pintype "passive"))
    )
    (net (code "71") (name "Net-(Q3-BASE)") (class "Default")
      (node (ref "Q3") (pin "1") (pinfunction "BASE_1") (pintype "passive"))
      (node (ref "R73") (pin "1") (pinfunction "1_1") (pintype "passive"))
      (node (ref "R74") (pin "2") (pinfunction "2_2") (pintype "passive"))
    )
    (net (code "72") (name "Net-(Q3-COLLECTOR)") (class "Default")
      (node (ref "Q3") (pin "3") (pinfunction "COLLECTOR_3") (pintype "passive"))
      (node (ref "R65") (pin "2") (pinfunction "2_2") (pintype "passive"))
    )
    (net (code "73") (name "Net-(Q5-BASE)") (class "Default")
      (node (ref "Q5") (pin "1") (pinfunction "BASE_1") (pintype "passive"))
      (node (ref "R82") (pin "1") (pinfunction "1_1") (pintype "passive"))
      (node (ref "R83") (pin "2") (pinfunction "2_2") (pintype "passive"))
    )
    (net (code "74") (name "Net-(Q5-COLLECTOR)") (class "Default")
      (node (ref "Q5") (pin "3") (pinfunction "COLLECTOR_3") (pintype "passive"))
      (node (ref "R80") (pin "1") (pinfunction "1_1") (pintype "passive"))
    )
    (net (code "75") (name "Net-(T1-MCT1)") (class "Default")
      (node (ref "R32") (pin "1") (pinfunction "1_1") (pintype "passive"))
      (node (ref "T1") (pin "24") (pinfunction "MCT1_24") (pintype "passive"))
    )
    (net (code "76") (name "Net-(T1-MCT2)") (class "Default")
      (node (ref "R26") (pin "1") (pinfunction "1_1") (pintype "passive"))
      (node (ref "T1") (pin "21") (pinfunction "MCT2_21") (pintype "passive"))
    )
    (net (code "77") (name "Net-(T1-MCT3)") (class "Default")
      (node (ref "R25") (pin "1") (pinfunction "1_1") (pintype "passive"))
      (node (ref "T1") (pin "18") (pinfunction "MCT3_18") (pintype "passive"))
    )
    (net (code "78") (name "Net-(T1-MCT4)") (class "Default")
      (node (ref "R24") (pin "1") (pinfunction "1_1") (pintype "passive"))
      (node (ref "T1") (pin "15") (pinfunction "MCT4_15") (pintype "passive"))
    )
    (net (code "79") (name "Net-(T1-TCT1)") (class "Default")
      (node (ref "C44") (pin "1") (pinfunction "1_1") (pintype "passive"))
      (node (ref "T1") (pin "1") (pinfunction "TCT1_1") (pintype "passive"))
      (node (ref "T1") (pin "10") (pinfunction "TCT4_10") (pintype "passive"))
      (node (ref "T1") (pin "4") (pinfunction "TCT2_4") (pintype "passive"))
      (node (ref "T1") (pin "7") (pinfunction "TCT3_7") (pintype "passive"))
    )
    (net (code "80") (name "Net-(TP1-TP)") (class "Default")
      (node (ref "TP1") (pin "1") (pinfunction "TP_1") (pintype "passive"))
      (node (ref "U8") (pin "46") (pinfunction "RSET/CLK125_46") (pintype "passive"))
    )
    (net (code "81") (name "Net-(U8-CKXTAL1)") (class "Default")
      (node (ref "R39") (pin "2") (pinfunction "2_2") (pintype "passive"))
      (node (ref "U8") (pin "42") (pinfunction "CKXTAL1_42") (pintype "input"))
    )
    (net (code "82") (name "Net-(U8-DVDD10_1)") (class "Default")
      (node (ref "B4") (pin "2") (pinfunction "2_2") (pintype "passive"))
      (node (ref "C38") (pin "1") (pinfunction "1_1") (pintype "passive"))
      (node (ref "C39") (pin "1") (pinfunction "1_1") (pintype "passive"))
      (node (ref "C40") (pin "1") (pinfunction "1_1") (pintype "passive"))
      (node (ref "L3") (pin "1") (pinfunction "1_1") (pintype "passive"))
      (node (ref "U8") (pin "28") (pinfunction "DVDD10_2_28") (pintype "power_in"))
      (node (ref "U8") (pin "36") (pinfunction "DVDD10_1_36") (pintype "power_in"))
    )
    (net (code "83") (name "Net-(U8-ENREG{slash}RSET)") (class "Default")
      (node (ref "R43") (pin "2") (pinfunction "2_2") (pintype "passive"))
      (node (ref "U8") (pin "39") (pinfunction "ENREG/RSET_39") (pintype "input"))
    )
    (net (code "84") (name "Net-(U8-PHYRSTB)") (class "Default")
      (node (ref "C54") (pin "2") (pinfunction "2_2") (pintype "passive"))
      (node (ref "R34") (pin "2") (pinfunction "2_2") (pintype "passive"))
      (node (ref "R35") (pin "2") (pinfunction "2_2") (pintype "passive"))
      (node (ref "U8") (pin "29") (pinfunction "PHYRSTB_29") (pintype "input"))
    )
    (net (code "85") (name "Net-(U8-REGOUT)") (class "Default")
      (node (ref "L3") (pin "2") (pinfunction "2_2") (pintype "passive"))
      (node (ref "U8") (pin "48") (pinfunction "REGOUT_48") (pintype "power_in"))
    )
    (net (code "86") (name "Net-(U8-VDDREG_1)") (class "Default")
      (node (ref "B3") (pin "1") (pinfunction "1_1") (pintype "passive"))
      (node (ref "C28") (pin "1") (pinfunction "1_1") (pintype "passive"))
      (node (ref "C29") (pin "1") (pinfunction "1_1") (pintype "passive"))
      (node (ref "C30") (pin "1") (pinfunction "1_1") (pintype "passive"))
      (node (ref "U8") (pin "44") (pinfunction "VDDREG_2_44") (pintype "power_in"))
      (node (ref "U8") (pin "45") (pinfunction "VDDREG_1_45") (pintype "power_in"))
    )
    (net (code "87") (name "Net-(U10-G)") (class "Default")
      (node (ref "R77") (pin "1") (pinfunction "1_1") (pintype "passive"))
      (node (ref "R80") (pin "2") (pinfunction "2_2") (pintype "passive"))
      (node (ref "U10") (pin "4") (pinfunction "G_4") (pintype "passive"))
    )
    (net (code "88") (name "unconnected-(JP1A-LVDS8-PadA14)") (class "Default")
      (node (ref "JP1") (pin "A14") (pinfunction "LVDS8_A14") (pintype "passive"))
    )
    (net (code "89") (name "unconnected-(JP1A-LVDS9-PadA15)") (class "Default")
      (node (ref "JP1") (pin "A15") (pinfunction "LVDS9_A15") (pintype "passive"))
    )
    (net (code "90") (name "unconnected-(JP1A-LVDS10-PadA16)") (class "Default")
      (node (ref "JP1") (pin "A16") (pinfunction "LVDS10_A16") (pintype "passive"))
    )
    (net (code "91") (name "unconnected-(JP1B-NC-PadB5)") (class "Default")
      (node (ref "JP1") (pin "B5") (pinfunction "NC_B5") (pintype "passive"))
    )
    (net (code "92") (name "unconnected-(JP1B-NC-PadB6)") (class "Default")
      (node (ref "JP1") (pin "B6") (pinfunction "NC_B6") (pintype "passive"))
    )
    (net (code "93") (name "unconnected-(JP1C-IO9-PadC4)") (class "Default")
      (node (ref "JP1") (pin "C4") (pinfunction "IO9_C4") (pintype "passive"))
    )
    (net (code "94") (name "unconnected-(JP1C-IO10-PadC5)") (class "Default")
      (node (ref "JP1") (pin "C5") (pinfunction "IO10_C5") (pintype "passive"))
    )
    (net (code "95") (name "unconnected-(JP1C-LVDSL7-PadC13)") (class "Default")
      (node (ref "JP1") (pin "C13") (pinfunction "LVDSL7_C13") (pintype "passive"))
    )
    (net (code "96") (name "unconnected-(JP1C-LVDSL8-PadC14)") (class "Default")
      (node (ref "JP1") (pin "C14") (pinfunction "LVDSL8_C14") (pintype "passive"))
    )
    (net (code "97") (name "unconnected-(JP1C-LVDSL9-PadC15)") (class "Default")
      (node (ref "JP1") (pin "C15") (pinfunction "LVDSL9_C15") (pintype "passive"))
    )
    (net (code "98") (name "unconnected-(JP1C-LVDSL10-PadC16)") (class "Default")
      (node (ref "JP1") (pin "C16") (pinfunction "LVDSL10_C16") (pintype "passive"))
    )
    (net (code "99") (name "unconnected-(U8-CKXTAL2-Pad43)") (class "Default")
      (node (ref "U8") (pin "43") (pinfunction "CKXTAL2_43") (pintype "output"))
    )
    (net (code "100") (name "unconnected-(U8-NC-Pad12)") (class "Default")
      (node (ref "U8") (pin "12") (pinfunction "NC_12") (pintype "passive"))
    )
  )
)
